# stm32h750xbh6-pwr.net
KiCad netlist of a schematic drawn in Altium Designer
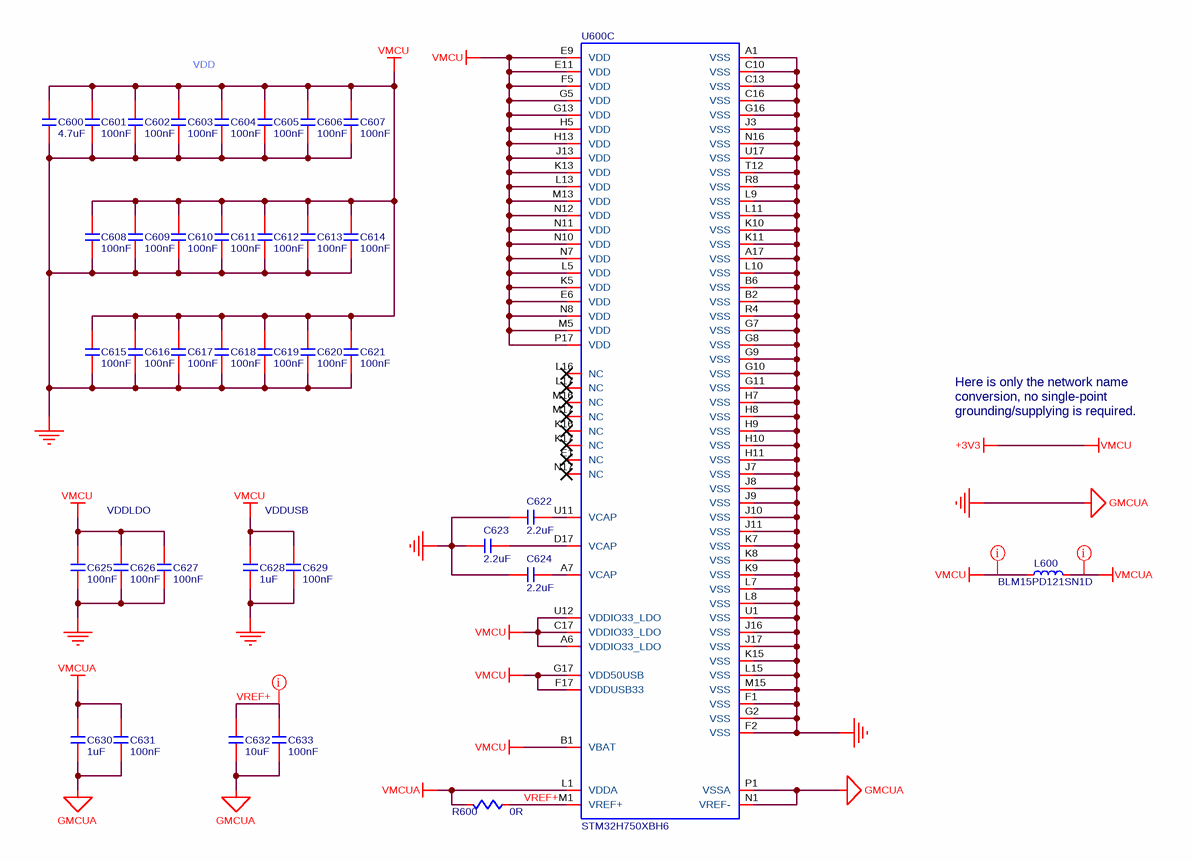
[diagram p0: stm32h750xbh6-pwr.SchDoc]

(export (version "E")
  (design (tool "Eeschema 10.0.6"))
  (components
    (comp (ref "C600")
      (value "4.7uF")
      (footprint "mw:C0603")
      (fields (field (name "VOLTAGE") "25V") (field (name "Comment") "C-NOMO"))
      (libsource (lib "mw") (part "C-NOMO"))
    )
    (comp (ref "C601")
      (value "100nF")
      (footprint "mw:C0402")
      (fields (field (name "VOLTAGE") "25V") (field (name "Comment") "C-NOMO"))
      (libsource (lib "mw") (part "C-NOMO"))
    )
    (comp (ref "C602")
      (value "100nF")
      (footprint "mw:C0402")
      (fields (field (name "VOLTAGE") "25V") (field (name "Comment") "C-NOMO"))
      (libsource (lib "mw") (part "C-NOMO"))
    )
    (comp (ref "C603")
      (value "100nF")
      (footprint "mw:C0402")
      (fields (field (name "VOLTAGE") "25V") (field (name "Comment") "C-NOMO"))
      (libsource (lib "mw") (part "C-NOMO"))
    )
    (comp (ref "C604")
      (value "100nF")
      (footprint "mw:C0402")
      (fields (field (name "VOLTAGE") "25V") (field (name "Comment") "C-NOMO"))
      (libsource (lib "mw") (part "C-NOMO"))
    )
    (comp (ref "C605")
      (value "100nF")
      (footprint "mw:C0402")
      (fields (field (name "VOLTAGE") "25V") (field (name "Comment") "C-NOMO"))
      (libsource (lib "mw") (part "C-NOMO"))
    )
    (comp (ref "C606")
      (value "100nF")
      (footprint "mw:C0402")
      (fields (field (name "VOLTAGE") "25V") (field (name "Comment") "C-NOMO"))
      (libsource (lib "mw") (part "C-NOMO"))
    )
    (comp (ref "C607")
      (value "100nF")
      (footprint "mw:C0402")
      (fields (field (name "VOLTAGE") "25V") (field (name "Comment") "C-NOMO"))
      (libsource (lib "mw") (part "C-NOMO"))
    )
    (comp (ref "C608")
      (value "100nF")
      (footprint "mw:C0402")
      (fields (field (name "VOLTAGE") "25V") (field (name "Comment") "C-NOMO"))
      (libsource (lib "mw") (part "C-NOMO"))
    )
    (comp (ref "C609")
      (value "100nF")
      (footprint "mw:C0402")
      (fields (field (name "VOLTAGE") "25V") (field (name "Comment") "C-NOMO"))
      (libsource (lib "mw") (part "C-NOMO"))
    )
    (comp (ref "C610")
      (value "100nF")
      (footprint "mw:C0402")
      (fields (field (name "VOLTAGE") "25V") (field (name "Comment") "C-NOMO"))
      (libsource (lib "mw") (part "C-NOMO"))
    )
    (comp (ref "C611")
      (value "100nF")
      (footprint "mw:C0402")
      (fields (field (name "VOLTAGE") "25V") (field (name "Comment") "C-NOMO"))
      (libsource (lib "mw") (part "C-NOMO"))
    )
    (comp (ref "C612")
      (value "100nF")
      (footprint "mw:C0402")
      (fields (field (name "VOLTAGE") "25V") (field (name "Comment") "C-NOMO"))
      (libsource (lib "mw") (part "C-NOMO"))
    )
    (comp (ref "C613")
      (value "100nF")
      (footprint "mw:C0402")
      (fields (field (name "VOLTAGE") "25V") (field (name "Comment") "C-NOMO"))
      (libsource (lib "mw") (part "C-NOMO"))
    )
    (comp (ref "C614")
      (value "100nF")
      (footprint "mw:C0402")
      (fields (field (name "VOLTAGE") "25V") (field (name "Comment") "C-NOMO"))
      (libsource (lib "mw") (part "C-NOMO"))
    )
    (comp (ref "C615")
      (value "100nF")
      (footprint "mw:C0402")
      (fields (field (name "VOLTAGE") "25V") (field (name "Comment") "C-NOMO"))
      (libsource (lib "mw") (part "C-NOMO"))
    )
    (comp (ref "C616")
      (value "100nF")
      (footprint "mw:C0402")
      (fields (field (name "VOLTAGE") "25V") (field (name "Comment") "C-NOMO"))
      (libsource (lib "mw") (part "C-NOMO"))
    )
    (comp (ref "C617")
      (value "100nF")
      (footprint "mw:C0402")
      (fields (field (name "VOLTAGE") "25V") (field (name "Comment") "C-NOMO"))
      (libsource (lib "mw") (part "C-NOMO"))
    )
    (comp (ref "C618")
      (value "100nF")
      (footprint "mw:C0402")
      (fields (field (name "VOLTAGE") "25V") (field (name "Comment") "C-NOMO"))
      (libsource (lib "mw") (part "C-NOMO"))
    )
    (comp (ref "C619")
      (value "100nF")
      (footprint "mw:C0402")
      (fields (field (name "VOLTAGE") "25V") (field (name "Comment") "C-NOMO"))
      (libsource (lib "mw") (part "C-NOMO"))
    )
    (comp (ref "C620")
      (value "100nF")
      (footprint "mw:C0402")
      (fields (field (name "VOLTAGE") "25V") (field (name "Comment") "C-NOMO"))
      (libsource (lib "mw") (part "C-NOMO"))
    )
    (comp (ref "C621")
      (value "100nF")
      (footprint "mw:C0402")
      (fields (field (name "VOLTAGE") "25V") (field (name "Comment") "C-NOMO"))
      (libsource (lib "mw") (part "C-NOMO"))
    )
    (comp (ref "C622")
      (value "2.2uF")
      (footprint "mw:C0603")
      (fields (field (name "VOLTAGE") "25V") (field (name "Comment") "C-NOMO"))
      (libsource (lib "mw") (part "C-NOMO"))
    )
    (comp (ref "C623")
      (value "2.2uF")
      (footprint "mw:C0603")
      (fields (field (name "VOLTAGE") "25V") (field (name "Comment") "C-NOMO"))
      (libsource (lib "mw") (part "C-NOMO"))
    )
    (comp (ref "C624")
      (value "2.2uF")
      (footprint "mw:C0603")
      (fields (field (name "VOLTAGE") "25V") (field (name "Comment") "C-NOMO"))
      (libsource (lib "mw") (part "C-NOMO"))
    )
    (comp (ref "C625")
      (value "100nF")
      (footprint "mw:C0402")
      (fields (field (name "VOLTAGE") "25V") (field (name "Comment") "C-NOMO"))
      (libsource (lib "mw") (part "C-NOMO"))
    )
    (comp (ref "C626")
      (value "100nF")
      (footprint "mw:C0402")
      (fields (field (name "VOLTAGE") "25V") (field (name "Comment") "C-NOMO"))
      (libsource (lib "mw") (part "C-NOMO"))
    )
    (comp (ref "C627")
      (value "100nF")
      (footprint "mw:C0402")
      (fields (field (name "VOLTAGE") "25V") (field (name "Comment") "C-NOMO"))
      (libsource (lib "mw") (part "C-NOMO"))
    )
    (comp (ref "C628")
      (value "1uF")
      (footprint "mw:C0603")
      (fields (field (name "VOLTAGE") "25V") (field (name "Comment") "C-NOMO"))
      (libsource (lib "mw") (part "C-NOMO"))
    )
    (comp (ref "C629")
      (value "100nF")
      (footprint "mw:C0402")
      (fields (field (name "VOLTAGE") "25V") (field (name "Comment") "C-NOMO"))
      (libsource (lib "mw") (part "C-NOMO"))
    )
    (comp (ref "C630")
      (value "1uF")
      (footprint "mw:C0603")
      (fields (field (name "VOLTAGE") "25V") (field (name "Comment") "C-NOMO"))
      (libsource (lib "mw") (part "C-NOMO"))
    )
    (comp (ref "C631")
      (value "100nF")
      (footprint "mw:C0402")
      (fields (field (name "VOLTAGE") "25V") (field (name "Comment") "C-NOMO"))
      (libsource (lib "mw") (part "C-NOMO"))
    )
    (comp (ref "C632")
      (value "10uF")
      (footprint "mw:C0805")
      (fields (field (name "VOLTAGE") "25V") (field (name "Comment") "C-NOMO"))
      (libsource (lib "mw") (part "C-NOMO"))
    )
    (comp (ref "C633")
      (value "100nF")
      (footprint "mw:C0402")
      (fields (field (name "VOLTAGE") "25V") (field (name "Comment") "C-NOMO"))
      (libsource (lib "mw") (part "C-NOMO"))
    )
    (comp (ref "L600")
      (value "BLM15PD121SN1D")
      (footprint "mw:L0402")
      (fields (field (name "PUBLISHER") "Altium Limited"))
      (libsource (lib "mw") (part "L"))
    )
    (comp (ref "R600")
      (value "0R")
      (footprint "mw:R0603")
      (fields (field (name "Comment") "R"))
      (libsource (lib "mw") (part "R"))
    )
    (comp (ref "U600")
      (value "STM32H750XBH6")
      (footprint "mw:STM32H750XBH6")
      (description "MCU")
      (libsource (lib "mw") (part "STM32H750XBH6"))
    )
  )
  (nets
    (net (code "1") (name "+3V3") (class "Default")
      (node (ref "C600") (pin "2") (pinfunction "2_2") (pintype "passive"))
      (node (ref "C601") (pin "2") (pinfunction "2_2") (pintype "passive"))
      (node (ref "C602") (pin "2") (pinfunction "2_2") (pintype "passive"))
      (node (ref "C603") (pin "2") (pinfunction "2_2") (pintype "passive"))
      (node (ref "C604") (pin "2") (pinfunction "2_2") (pintype "passive"))
      (node (ref "C605") (pin "2") (pinfunction "2_2") (pintype "passive"))
      (node (ref "C606") (pin "2") (pinfunction "2_2") (pintype "passive"))
      (node (ref "C607") (pin "2") (pinfunction "2_2") (pintype "passive"))
      (node (ref "C608") (pin "2") (pinfunction "2_2") (pintype "passive"))
      (node (ref "C609") (pin "2") (pinfunction "2_2") (pintype "passive"))
      (node (ref "C610") (pin "2") (pinfunction "2_2") (pintype "passive"))
      (node (ref "C611") (pin "2") (pinfunction "2_2") (pintype "passive"))
      (node (ref "C612") (pin "2") (pinfunction "2_2") (pintype "passive"))
      (node (ref "C613") (pin "2") (pinfunction "2_2") (pintype "passive"))
      (node (ref "C614") (pin "2") (pinfunction "2_2") (pintype "passive"))
      (node (ref "C615") (pin "2") (pinfunction "2_2") (pintype "passive"))
      (node (ref "C616") (pin "2") (pinfunction "2_2") (pintype "passive"))
      (node (ref "C617") (pin "2") (pinfunction "2_2") (pintype "passive"))
      (node (ref "C618") (pin "2") (pinfunction "2_2") (pintype "passive"))
      (node (ref "C619") (pin "2") (pinfunction "2_2") (pintype "passive"))
      (node (ref "C620") (pin "2") (pinfunction "2_2") (pintype "passive"))
      (node (ref "C621") (pin "2") (pinfunction "2_2") (pintype "passive"))
      (node (ref "C625") (pin "2") (pinfunction "2_2") (pintype "passive"))
      (node (ref "C626") (pin "2") (pinfunction "2_2") (pintype "passive"))
      (node (ref "C627") (pin "2") (pinfunction "2_2") (pintype "passive"))
      (node (ref "C628") (pin "2") (pinfunction "2_2") (pintype "passive"))
      (node (ref "C629") (pin "2") (pinfunction "2_2") (pintype "passive"))
      (node (ref "L600") (pin "1") (pinfunction "1_1") (pintype "passive"))
      (node (ref "U600") (pin "A6") (pinfunction "VDDIO33_LDO_A6") (pintype "passive"))
      (node (ref "U600") (pin "B1") (pinfunction "VBAT_B1") (pintype "passive"))
      (node (ref "U600") (pin "C17") (pinfunction "VDDIO33_LDO_C17") (pintype "passive"))
      (node (ref "U600") (pin "E11") (pinfunction "VDD_E11") (pintype "passive"))
      (node (ref "U600") (pin "E6") (pinfunction "VDD_E6") (pintype "passive"))
      (node (ref "U600") (pin "E9") (pinfunction "VDD_E9") (pintype "passive"))
      (node (ref "U600") (pin "F17") (pinfunction "VDDUSB33_F17") (pintype "passive"))
      (node (ref "U600") (pin "F5") (pinfunction "VDD_F5") (pintype "passive"))
      (node (ref "U600") (pin "G13") (pinfunction "VDD_G13") (pintype "passive"))
      (node (ref "U600") (pin "G17") (pinfunction "VDD50USB_G17") (pintype "passive"))
      (node (ref "U600") (pin "G5") (pinfunction "VDD_G5") (pintype "passive"))
      (node (ref "U600") (pin "H13") (pinfunction "VDD_H13") (pintype "passive"))
      (node (ref "U600") (pin "H5") (pinfunction "VDD_H5") (pintype "passive"))
      (node (ref "U600") (pin "J13") (pinfunction "VDD_J13") (pintype "passive"))
      (node (ref "U600") (pin "K13") (pinfunction "VDD_K13") (pintype "passive"))
      (node (ref "U600") (pin "K5") (pinfunction "VDD_K5") (pintype "passive"))
      (node (ref "U600") (pin "L13") (pinfunction "VDD_L13") (pintype "passive"))
      (node (ref "U600") (pin "L5") (pinfunction "VDD_L5") (pintype "passive"))
      (node (ref "U600") (pin "M13") (pinfunction "VDD_M13") (pintype "passive"))
      (node (ref "U600") (pin "M5") (pinfunction "VDD_M5") (pintype "passive"))
      (node (ref "U600") (pin "N10") (pinfunction "VDD_N10") (pintype "passive"))
      (node (ref "U600") (pin "N11") (pinfunction "VDD_N11") (pintype "passive"))
      (node (ref "U600") (pin "N12") (pinfunction "VDD_N12") (pintype "passive"))
      (node (ref "U600") (pin "N7") (pinfunction "VDD_N7") (pintype "passive"))
      (node (ref "U600") (pin "N8") (pinfunction "VDD_N8") (pintype "passive"))
      (node (ref "U600") (pin "P17") (pinfunction "VDD_P17") (pintype "passive"))
      (node (ref "U600") (pin "U12") (pinfunction "VDDIO33_LDO_U12") (pintype "passive"))
    )
    (net (code "2") (name "/VREF+") (class "Default")
      (node (ref "C632") (pin "2") (pinfunction "2_2") (pintype "passive"))
      (node (ref "C633") (pin "2") (pinfunction "2_2") (pintype "passive"))
      (node (ref "R600") (pin "2") (pinfunction "2_2") (pintype "passive"))
      (node (ref "U600") (pin "M1") (pinfunction "VREF+_M1") (pintype "passive"))
    )
    (net (code "3") (name "GMCUA") (class "Default")
      (node (ref "C600") (pin "1") (pinfunction "1_1") (pintype "passive"))
      (node (ref "C601") (pin "1") (pinfunction "1_1") (pintype "passive"))
      (node (ref "C602") (pin "1") (pinfunction "1_1") (pintype "passive"))
      (node (ref "C603") (pin "1") (pinfunction "1_1") (pintype "passive"))
      (node (ref "C604") (pin "1") (pinfunction "1_1") (pintype "passive"))
      (node (ref "C605") (pin "1") (pinfunction "1_1") (pintype "passive"))
      (node (ref "C606") (pin "1") (pinfunction "1_1") (pintype "passive"))
      (node (ref "C607") (pin "1") (pinfunction "1_1") (pintype "passive"))
      (node (ref "C608") (pin "1") (pinfunction "1_1") (pintype "passive"))
      (node (ref "C609") (pin "1") (pinfunction "1_1") (pintype "passive"))
      (node (ref "C610") (pin "1") (pinfunction "1_1") (pintype "passive"))
      (node (ref "C611") (pin "1") (pinfunction "1_1") (pintype "passive"))
      (node (ref "C612") (pin "1") (pinfunction "1_1") (pintype "passive"))
      (node (ref "C613") (pin "1") (pinfunction "1_1") (pintype "passive"))
      (node (ref "C614") (pin "1") (pinfunction "1_1") (pintype "passive"))
      (node (ref "C615") (pin "1") (pinfunction "1_1") (pintype "passive"))
      (node (ref "C616") (pin "1") (pinfunction "1_1") (pintype "passive"))
      (node (ref "C617") (pin "1") (pinfunction "1_1") (pintype "passive"))
      (node (ref "C618") (pin "1") (pinfunction "1_1") (pintype "passive"))
      (node (ref "C619") (pin "1") (pinfunction "1_1") (pintype "passive"))
      (node (ref "C620") (pin "1") (pinfunction "1_1") (pintype "passive"))
      (node (ref "C621") (pin "1") (pinfunction "1_1") (pintype "passive"))
      (node (ref "C622") (pin "1") (pinfunction "1_1") (pintype "passive"))
      (node (ref "C623") (pin "1") (pinfunction "1_1") (pintype "passive"))
      (node (ref "C624") (pin "1") (pinfunction "1_1") (pintype "passive"))
      (node (ref "C625") (pin "1") (pinfunction "1_1") (pintype "passive"))
      (node (ref "C626") (pin "1") (pinfunction "1_1") (pintype "passive"))
      (node (ref "C627") (pin "1") (pinfunction "1_1") (pintype "passive"))
      (node (ref "C628") (pin "1") (pinfunction "1_1") (pintype "passive"))
      (node (ref "C629") (pin "1") (pinfunction "1_1") (pintype "passive"))
      (node (ref "C630") (pin "1") (pinfunction "1_1") (pintype "passive"))
      (node (ref "C631") (pin "1") (pinfunction "1_1") (pintype "passive"))
      (node (ref "C632") (pin "1") (pinfunction "1_1") (pintype "passive"))
      (node (ref "C633") (pin "1") (pinfunction "1_1") (pintype "passive"))
      (node (ref "U600") (pin "A1") (pinfunction "VSS_A1") (pintype "passive"))
      (node (ref "U600") (pin "A17") (pinfunction "VSS_A17") (pintype "passive"))
      (node (ref "U600") (pin "B2") (pinfunction "VSS_B2") (pintype "passive"))
      (node (ref "U600") (pin "B6") (pinfunction "VSS_B6") (pintype "passive"))
      (node (ref "U600") (pin "C10") (pinfunction "VSS_C10") (pintype "passive"))
      (node (ref "U600") (pin "C13") (pinfunction "VSS_C13") (pintype "passive"))
      (node (ref "U600") (pin "C16") (pinfunction "VSS_C16") (pintype "passive"))
      (node (ref "U600") (pin "F1") (pinfunction "VSS_F1") (pintype "passive"))
      (node (ref "U600") (pin "F2") (pinfunction "VSS_F2") (pintype "passive"))
      (node (ref "U600") (pin "G10") (pinfunction "VSS_G10") (pintype "passive"))
      (node (ref "U600") (pin "G11") (pinfunction "VSS_G11") (pintype "passive"))
      (node (ref "U600") (pin "G16") (pinfunction "VSS_G16") (pintype "passive"))
      (node (ref "U600") (pin "G2") (pinfunction "VSS_G2") (pintype "passive"))
      (node (ref "U600") (pin "G7") (pinfunction "VSS_G7") (pintype "passive"))
      (node (ref "U600") (pin "G8") (pinfunction "VSS_G8") (pintype "passive"))
      (node (ref "U600") (pin "G9") (pinfunction "VSS_G9") (pintype "passive"))
      (node (ref "U600") (pin "H10") (pinfunction "VSS_H10") (pintype "passive"))
      (node (ref "U600") (pin "H11") (pinfunction "VSS_H11") (pintype "passive"))
      (node (ref "U600") (pin "H7") (pinfunction "VSS_H7") (pintype "passive"))
      (node (ref "U600") (pin "H8") (pinfunction "VSS_H8") (pintype "passive"))
      (node (ref "U600") (pin "H9") (pinfunction "VSS_H9") (pintype "passive"))
      (node (ref "U600") (pin "J10") (pinfunction "VSS_J10") (pintype "passive"))
      (node (ref "U600") (pin "J11") (pinfunction "VSS_J11") (pintype "passive"))
      (node (ref "U600") (pin "J16") (pinfunction "VSS_J16") (pintype "passive"))
      (node (ref "U600") (pin "J17") (pinfunction "VSS_J17") (pintype "passive"))
      (node (ref "U600") (pin "J3") (pinfunction "VSS_J3") (pintype "passive"))
      (node (ref "U600") (pin "J7") (pinfunction "VSS_J7") (pintype "passive"))
      (node (ref "U600") (pin "J8") (pinfunction "VSS_J8") (pintype "passive"))
      (node (ref "U600") (pin "J9") (pinfunction "VSS_J9") (pintype "passive"))
      (node (ref "U600") (pin "K10") (pinfunction "VSS_K10") (pintype "passive"))
      (node (ref "U600") (pin "K11") (pinfunction "VSS_K11") (pintype "passive"))
      (node (ref "U600") (pin "K15") (pinfunction "VSS_K15") (pintype "passive"))
      (node (ref "U600") (pin "K7") (pinfunction "VSS_K7") (pintype "passive"))
      (node (ref "U600") (pin "K8") (pinfunction "VSS_K8") (pintype "passive"))
      (node (ref "U600") (pin "K9") (pinfunction "VSS_K9") (pintype "passive"))
      (node (ref "U600") (pin "L10") (pinfunction "VSS_L10") (pintype "passive"))
      (node (ref "U600") (pin "L11") (pinfunction "VSS_L11") (pintype "passive"))
      (node (ref "U600") (pin "L15") (pinfunction "VSS_L15") (pintype "passive"))
      (node (ref "U600") (pin "L7") (pinfunction "VSS_L7") (pintype "passive"))
      (node (ref "U600") (pin "L8") (pinfunction "VSS_L8") (pintype "passive"))
      (node (ref "U600") (pin "L9") (pinfunction "VSS_L9") (pintype "passive"))
      (node (ref "U600") (pin "M15") (pinfunction "VSS_M15") (pintype "passive"))
      (node (ref "U600") (pin "N1") (pinfunction "VREF-_N1") (pintype "passive"))
      (node (ref "U600") (pin "N16") (pinfunction "VSS_N16") (pintype "passive"))
      (node (ref "U600") (pin "P1") (pinfunction "VSSA_P1") (pintype "passive"))
      (node (ref "U600") (pin "R4") (pinfunction "VSS_R4") (pintype "passive"))
      (node (ref "U600") (pin "R8") (pinfunction "VSS_R8") (pintype "passive"))
      (node (ref "U600") (pin "T12") (pinfunction "VSS_T12") (pintype "passive"))
      (node (ref "U600") (pin "U1") (pinfunction "VSS_U1") (pintype "passive"))
      (node (ref "U600") (pin "U17") (pinfunction "VSS_U17") (pintype "passive"))
    )
    (net (code "4") (name "Net-(C622-Pad2)") (class "Default")
      (node (ref "C622") (pin "2") (pinfunction "2_2") (pintype "passive"))
      (node (ref "U600") (pin "U11") (pinfunction "VCAP_U11") (pintype "passive"))
    )
    (net (code "5") (name "Net-(C623-Pad2)") (class "Default")
      (node (ref "C623") (pin "2") (pinfunction "2_2") (pintype "passive"))
      (node (ref "U600") (pin "D17") (pinfunction "VCAP_D17") (pintype "passive"))
    )
    (net (code "6") (name "Net-(C624-Pad2)") (class "Default")
      (node (ref "C624") (pin "2") (pinfunction "2_2") (pintype "passive"))
      (node (ref "U600") (pin "A7") (pinfunction "VCAP_A7") (pintype "passive"))
    )
    (net (code "7") (name "VMCUA") (class "Default")
      (node (ref "C630") (pin "2") (pinfunction "2_2") (pintype "passive"))
      (node (ref "C631") (pin "2") (pinfunction "2_2") (pintype "passive"))
      (node (ref "L600") (pin "2") (pinfunction "2_2") (pintype "passive"))
      (node (ref "R600") (pin "1") (pinfunction "1_1") (pintype "passive"))
      (node (ref "U600") (pin "L1") (pinfunction "VDDA_L1") (pintype "passive"))
    )
    (net (code "8") (name "unconnected-(U600C-NC-PadE1)") (class "Default")
      (node (ref "U600") (pin "E1") (pinfunction "NC_E1") (pintype "passive+no_connect"))
    )
    (net (code "9") (name "unconnected-(U600C-NC-PadK16)") (class "Default")
      (node (ref "U600") (pin "K16") (pinfunction "NC_K16") (pintype "passive+no_connect"))
    )
    (net (code "10") (name "unconnected-(U600C-NC-PadK17)") (class "Default")
      (node (ref "U600") (pin "K17") (pinfunction "NC_K17") (pintype "passive+no_connect"))
    )
    (net (code "11") (name "unconnected-(U600C-NC-PadL16)") (class "Default")
      (node (ref "U600") (pin "L16") (pinfunction "NC_L16") (pintype "passive+no_connect"))
    )
    (net (code "12") (name "unconnected-(U600C-NC-PadL17)") (class "Default")
      (node (ref "U600") (pin "L17") (pinfunction "NC_L17") (pintype "passive+no_connect"))
    )
    (net (code "13") (name "unconnected-(U600C-NC-PadM16)") (class "Default")
      (node (ref "U600") (pin "M16") (pinfunction "NC_M16") (pintype "passive+no_connect"))
    )
    (net (code "14") (name "unconnected-(U600C-NC-PadM17)") (class "Default")
      (node (ref "U600") (pin "M17") (pinfunction "NC_M17") (pintype "passive+no_connect"))
    )
    (net (code "15") (name "unconnected-(U600C-NC-PadN17)") (class "Default")
      (node (ref "U600") (pin "N17") (pinfunction "NC_N17") (pintype "passive+no_connect"))
    )
  )
)
